# mipi_serializer2.net
KiCad netlist of a schematic drawn in Altium Designer
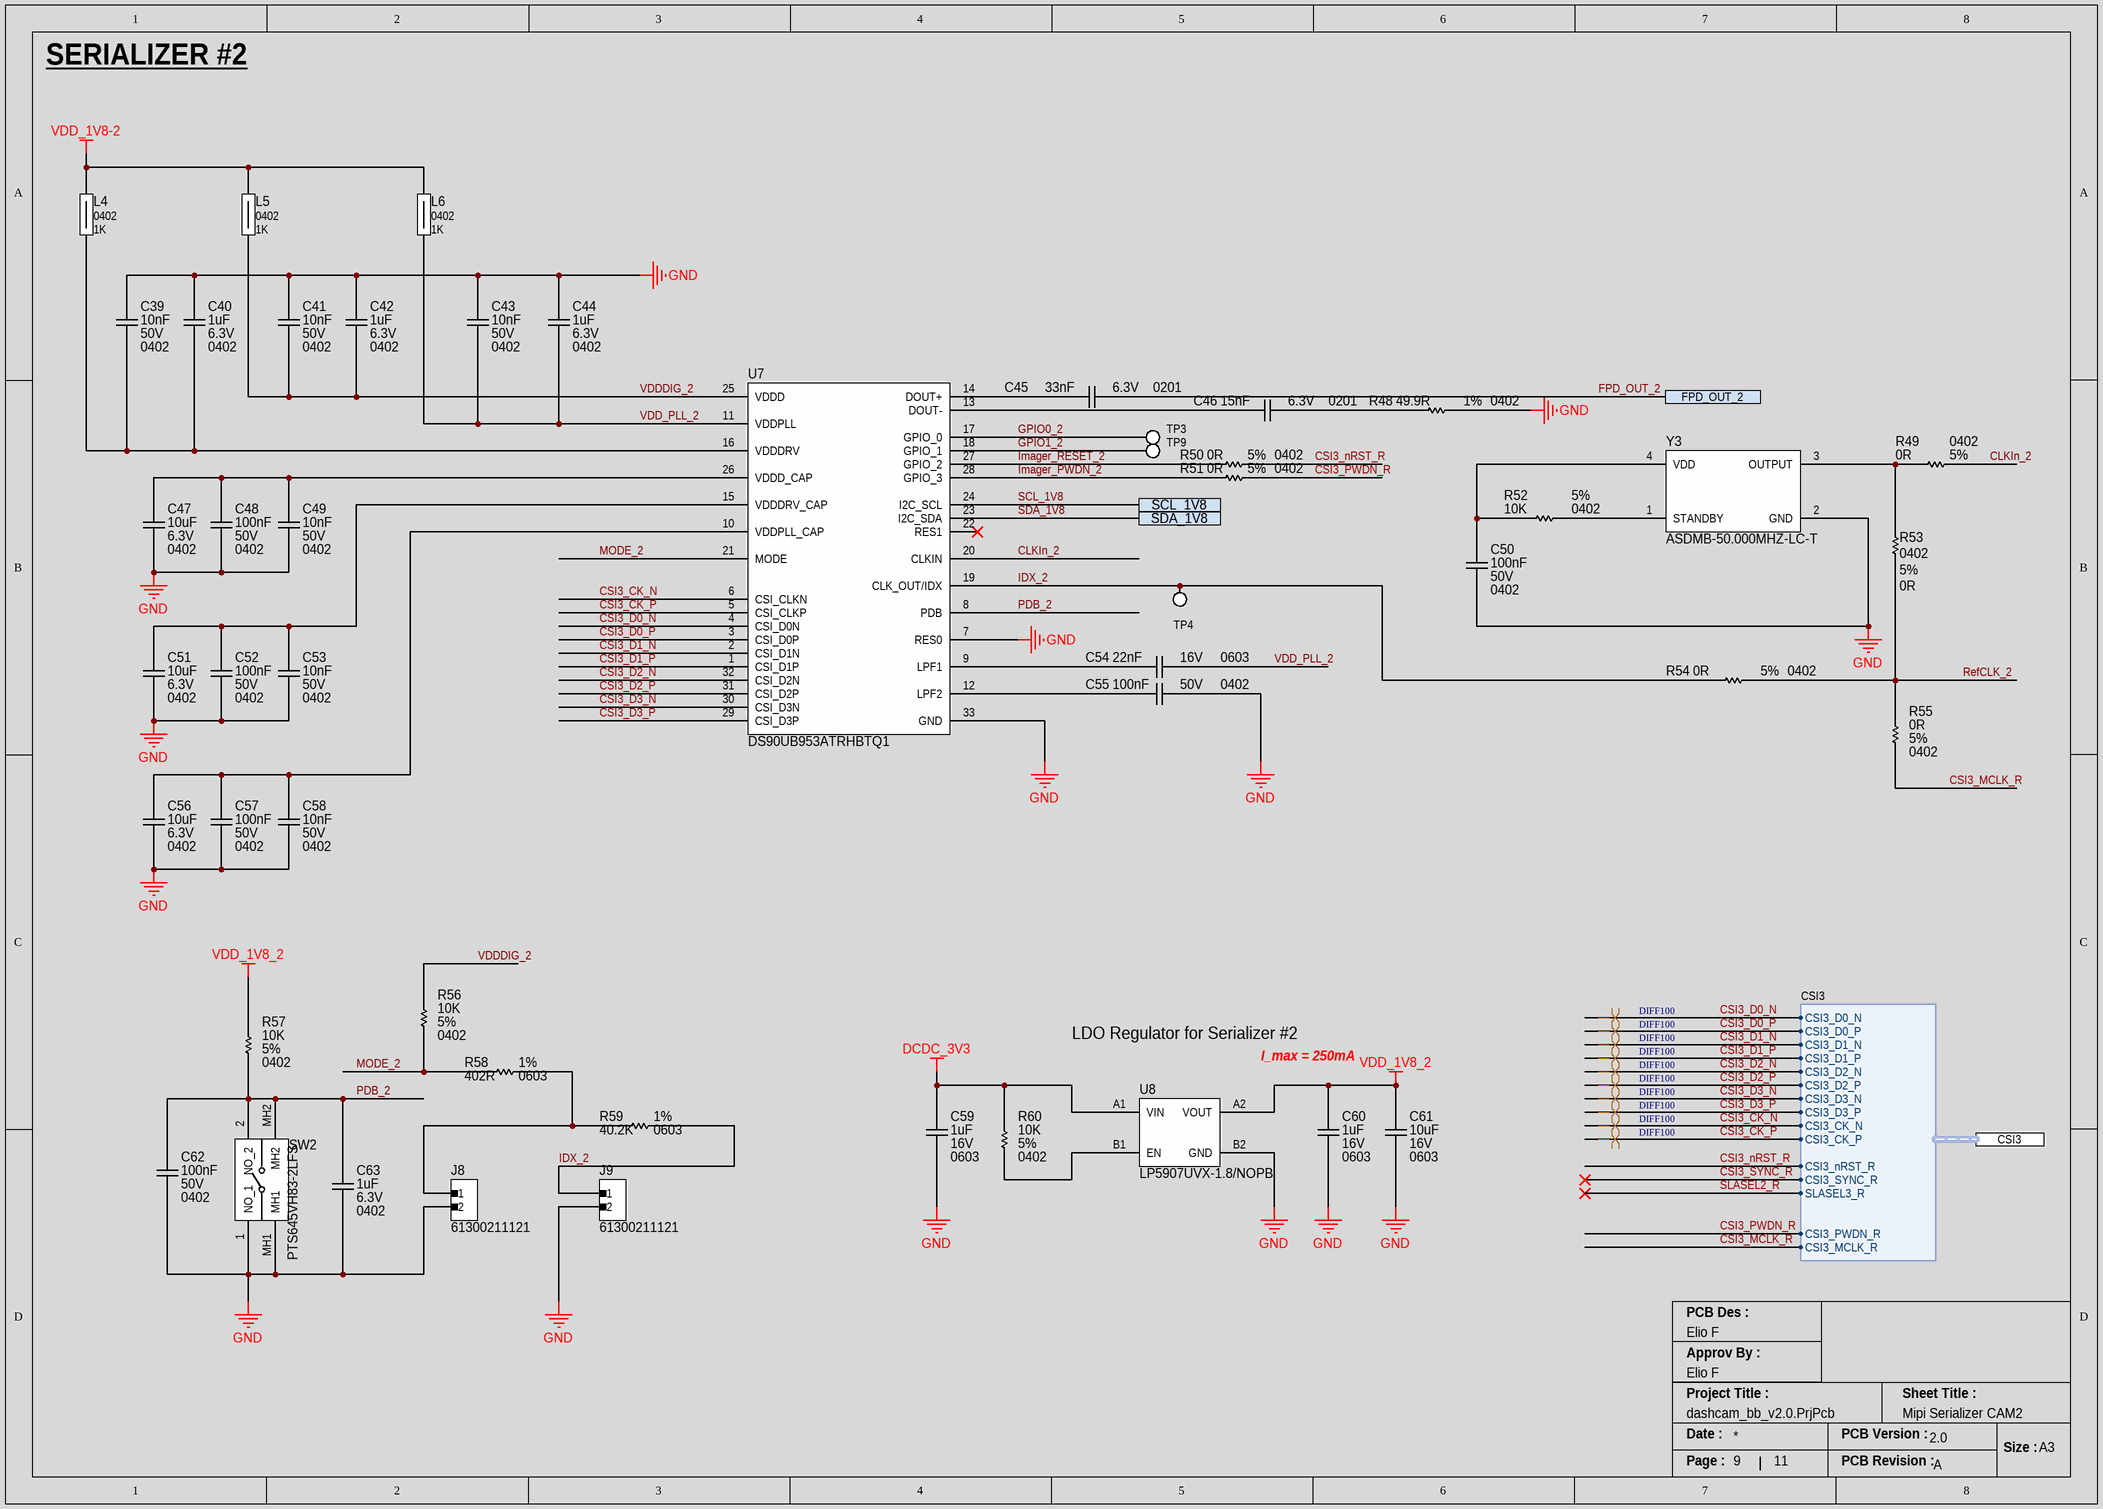
[diagram p0: mipi_serializer2.SchDoc]

(export (version "E")
  (design (tool "Eeschema 10.0.6"))
  (components
    (comp (ref "C39")
      (value "GRM155R71H103KA88D")
      (footprint "CAP_0402_CAPC1005X05N")
      (description "Multilayer Ceramic Capacitors MLCC Surface Mount 0402 0.01uF 50 Volts X7R 10%")
      (fields
        (field (name "MANUFACTURER") "Murata")
        (field (name "TOLERANCE") "10%")
        (field (name "VOLTAGE RATING") "50V")
        (field (name "CAPACITANCE") "10nF")
        (field (name "CASE/PACKAGE") "0402")
      )
      (libsource (lib "Electronic Devices_LIB") (part "CAP_10nF_50V_X7R_0402"))
    )
    (comp (ref "C40")
      (value "CL05B105KQ5NQNC")
      (footprint "CAP_0402_CAPC1005X05N")
      (description "Multilayer Ceramic Capacitor, 1 uF, 6.3 V, ï¿½ 10%, X7R, 0402 [1005 Metric]")
      (fields
        (field (name "MANUFACTURER") "Samsung")
        (field (name "TOLERANCE") "10%")
        (field (name "CAPACITANCE") "1uF")
        (field (name "VOLTAGE RATING") "6.3V")
        (field (name "CASE CODE (IMPERIAL)") "0402")
      )
      (libsource (lib "Electronic Devices_LIB") (part "CAP_1uF_6.3V_X7R_0402"))
    )
    (comp (ref "C41")
      (value "GRM155R71H103KA88D")
      (footprint "CAP_0402_CAPC1005X05N")
      (description "Multilayer Ceramic Capacitors MLCC Surface Mount 0402 0.01uF 50 Volts X7R 10%")
      (fields
        (field (name "MANUFACTURER") "Murata")
        (field (name "TOLERANCE") "10%")
        (field (name "VOLTAGE RATING") "50V")
        (field (name "CAPACITANCE") "10nF")
        (field (name "CASE/PACKAGE") "0402")
      )
      (libsource (lib "Electronic Devices_LIB") (part "CAP_10nF_50V_X7R_0402"))
    )
    (comp (ref "C42")
      (value "CL05B105KQ5NQNC")
      (footprint "CAP_0402_CAPC1005X05N")
      (description "Multilayer Ceramic Capacitor, 1 uF, 6.3 V, ï¿½ 10%, X7R, 0402 [1005 Metric]")
      (fields
        (field (name "MANUFACTURER") "Samsung")
        (field (name "TOLERANCE") "10%")
        (field (name "CAPACITANCE") "1uF")
        (field (name "VOLTAGE RATING") "6.3V")
        (field (name "CASE CODE (IMPERIAL)") "0402")
      )
      (libsource (lib "Electronic Devices_LIB") (part "CAP_1uF_6.3V_X7R_0402"))
    )
    (comp (ref "C43")
      (value "GRM155R71H103KA88D")
      (footprint "CAP_0402_CAPC1005X05N")
      (description "Multilayer Ceramic Capacitors MLCC Surface Mount 0402 0.01uF 50 Volts X7R 10%")
      (fields
        (field (name "MANUFACTURER") "Murata")
        (field (name "TOLERANCE") "10%")
        (field (name "VOLTAGE RATING") "50V")
        (field (name "CAPACITANCE") "10nF")
        (field (name "CASE/PACKAGE") "0402")
      )
      (libsource (lib "Electronic Devices_LIB") (part "CAP_10nF_50V_X7R_0402"))
    )
    (comp (ref "C44")
      (value "CL05B105KQ5NQNC")
      (footprint "CAP_0402_CAPC1005X05N")
      (description "Multilayer Ceramic Capacitor, 1 uF, 6.3 V, ï¿½ 10%, X7R, 0402 [1005 Metric]")
      (fields
        (field (name "MANUFACTURER") "Samsung")
        (field (name "TOLERANCE") "10%")
        (field (name "CAPACITANCE") "1uF")
        (field (name "VOLTAGE RATING") "6.3V")
        (field (name "CASE CODE (IMPERIAL)") "0402")
      )
      (libsource (lib "Electronic Devices_LIB") (part "CAP_1uF_6.3V_X7R_0402"))
    )
    (comp (ref "C45")
      (value "GRM033R60J333KE01D")
      (footprint "CAP_0201_CAPC0603X03N")
      (description "Multilayer Ceramic Capacitor, 0.033 uF, 6.3 V, ± 10%, X5R, 0201 [0603 Metric]")
      (fields
        (field (name "MANUFACTURER") "Murata")
        (field (name "TOLERANCE") "10%")
        (field (name "VOLTAGE RATING") "6.3V")
        (field (name "CAPACITANCE") "33nF")
        (field (name "CASE/PACKAGE") "0201")
      )
      (libsource (lib "Electronic Devices_LIB") (part "CAP_0.033uF_6.3V_X5R_0201"))
    )
    (comp (ref "C46")
      (value "GRM033R60J153KE01D")
      (footprint "CAP_0201_CAPC0603X03N")
      (description "0201 15 nF 6.3 V ±10% Tolerance X5R SMT Multilayer Ceramic Capacitor")
      (fields
        (field (name "MANUFACTURER") "Murata")
        (field (name "TOLERANCE") "10%")
        (field (name "VOLTAGE RATING") "6.3V")
        (field (name "CAPACITANCE") "15nF")
        (field (name "CASE/PACKAGE") "0201")
      )
      (libsource (lib "Electronic Devices_LIB") (part "CAP_0.015uF_6.3V_X5R_0201"))
    )
    (comp (ref "C47")
      (value "CL05A106MQ5NUNC")
      (footprint "CAP_0402_CAPC1005X05N")
      (description "Cap Ceramic 10uF 6.3V X5R 20% SMD 0402 85C T/R")
      (fields
        (field (name "MANUFACTURER") "Samsung")
        (field (name "TOLERANCE") "20%")
        (field (name "CASE/PACKAGE") "0402")
        (field (name "CAPACITANCE") "10uF")
        (field (name "VOLTAGE RATING") "6.3V")
      )
      (libsource (lib "Electronic Devices_LIB") (part "CAP_10UF_6.3V_X5R_0402"))
    )
    (comp (ref "C48")
      (value "GRM155R71H104KE14D")
      (footprint "CAP_0402_CAPC1005X05N")
      (description "Multilayer Ceramic Capacitor, 0.1 uF, 16 V, ± 10%, X7R, 0402 [1005 Metric]")
      (fields
        (field (name "MANUFACTURER") "Murata")
        (field (name "TOLERANCE") "10%")
        (field (name "VOLTAGE RATING") "50V")
        (field (name "CAPACITANCE") "100nF")
        (field (name "CASE/PACKAGE") "0402")
      )
      (libsource (lib "Electronic Devices_LIB") (part "CAP_100NF_50V_X7R_0402"))
    )
    (comp (ref "C49")
      (value "GRM155R71H103KA88D")
      (footprint "CAP_0402_CAPC1005X05N")
      (description "Multilayer Ceramic Capacitors MLCC Surface Mount 0402 0.01uF 50 Volts X7R 10%")
      (fields
        (field (name "MANUFACTURER") "Murata")
        (field (name "TOLERANCE") "10%")
        (field (name "VOLTAGE RATING") "50V")
        (field (name "CAPACITANCE") "10nF")
        (field (name "CASE/PACKAGE") "0402")
      )
      (libsource (lib "Electronic Devices_LIB") (part "CAP_10nF_50V_X7R_0402"))
    )
    (comp (ref "C50")
      (value "GRM155R71H104KE14D")
      (footprint "CAP_0402_CAPC1005X05N")
      (description "Multilayer Ceramic Capacitor, 0.1 uF, 16 V, ± 10%, X7R, 0402 [1005 Metric]")
      (fields
        (field (name "MANUFACTURER") "Murata")
        (field (name "TOLERANCE") "10%")
        (field (name "VOLTAGE RATING") "50V")
        (field (name "CAPACITANCE") "100nF")
        (field (name "CASE/PACKAGE") "0402")
      )
      (libsource (lib "Electronic Devices_LIB") (part "CAP_100NF_50V_X7R_0402"))
    )
    (comp (ref "C51")
      (value "CL05A106MQ5NUNC")
      (footprint "CAP_0402_CAPC1005X05N")
      (description "Cap Ceramic 10uF 6.3V X5R 20% SMD 0402 85C T/R")
      (fields
        (field (name "MANUFACTURER") "Samsung")
        (field (name "TOLERANCE") "20%")
        (field (name "CASE/PACKAGE") "0402")
        (field (name "CAPACITANCE") "10uF")
        (field (name "VOLTAGE RATING") "6.3V")
      )
      (libsource (lib "Electronic Devices_LIB") (part "CAP_10UF_6.3V_X5R_0402"))
    )
    (comp (ref "C52")
      (value "GRM155R71H104KE14D")
      (footprint "CAP_0402_CAPC1005X05N")
      (description "Multilayer Ceramic Capacitor, 0.1 uF, 16 V, ± 10%, X7R, 0402 [1005 Metric]")
      (fields
        (field (name "MANUFACTURER") "Murata")
        (field (name "TOLERANCE") "10%")
        (field (name "VOLTAGE RATING") "50V")
        (field (name "CAPACITANCE") "100nF")
        (field (name "CASE/PACKAGE") "0402")
      )
      (libsource (lib "Electronic Devices_LIB") (part "CAP_100NF_50V_X7R_0402"))
    )
    (comp (ref "C53")
      (value "GRM155R71H103KA88D")
      (footprint "CAP_0402_CAPC1005X05N")
      (description "Multilayer Ceramic Capacitors MLCC Surface Mount 0402 0.01uF 50 Volts X7R 10%")
      (fields
        (field (name "MANUFACTURER") "Murata")
        (field (name "TOLERANCE") "10%")
        (field (name "VOLTAGE RATING") "50V")
        (field (name "CAPACITANCE") "10nF")
        (field (name "CASE/PACKAGE") "0402")
      )
      (libsource (lib "Electronic Devices_LIB") (part "CAP_10nF_50V_X7R_0402"))
    )
    (comp (ref "C54")
      (value "C0603C223K4RACTU")
      (footprint "CAP_0603_CAPC1608X08N")
      (description "Multilayer Ceramic Capacitor, 0.022 uF, 16 V, ± 10%, X7R, 0603 [1608 Metric]")
      (fields
        (field (name "MANUFACTURER") "KEMET")
        (field (name "TOLERANCE") "10%")
        (field (name "VOLTAGE RATING (DC)") "16V")
        (field (name "CAPACITANCE") "22nF")
        (field (name "CASE/PACKAGE") "0603")
      )
      (libsource (lib "Electronic Devices_LIB") (part "CAP_22nF_16V_X7R_0603"))
    )
    (comp (ref "C55")
      (value "GRM155R71H104KE14D")
      (footprint "CAP_0402_CAPC1005X05N")
      (description "Multilayer Ceramic Capacitor, 0.1 uF, 16 V, ± 10%, X7R, 0402 [1005 Metric]")
      (fields
        (field (name "MANUFACTURER") "Murata")
        (field (name "TOLERANCE") "10%")
        (field (name "VOLTAGE RATING") "50V")
        (field (name "CAPACITANCE") "100nF")
        (field (name "CASE/PACKAGE") "0402")
      )
      (libsource (lib "Electronic Devices_LIB") (part "CAP_100NF_50V_X7R_0402"))
    )
    (comp (ref "C56")
      (value "CL05A106MQ5NUNC")
      (footprint "CAP_0402_CAPC1005X05N")
      (description "Cap Ceramic 10uF 6.3V X5R 20% SMD 0402 85C T/R")
      (fields
        (field (name "MANUFACTURER") "Samsung")
        (field (name "TOLERANCE") "20%")
        (field (name "CASE/PACKAGE") "0402")
        (field (name "CAPACITANCE") "10uF")
        (field (name "VOLTAGE RATING") "6.3V")
      )
      (libsource (lib "Electronic Devices_LIB") (part "CAP_10UF_6.3V_X5R_0402"))
    )
    (comp (ref "C57")
      (value "GRM155R71H104KE14D")
      (footprint "CAP_0402_CAPC1005X05N")
      (description "Multilayer Ceramic Capacitor, 0.1 uF, 16 V, ± 10%, X7R, 0402 [1005 Metric]")
      (fields
        (field (name "MANUFACTURER") "Murata")
        (field (name "TOLERANCE") "10%")
        (field (name "VOLTAGE RATING") "50V")
        (field (name "CAPACITANCE") "100nF")
        (field (name "CASE/PACKAGE") "0402")
      )
      (libsource (lib "Electronic Devices_LIB") (part "CAP_100NF_50V_X7R_0402"))
    )
    (comp (ref "C58")
      (value "GRM155R71H103KA88D")
      (footprint "CAP_0402_CAPC1005X05N")
      (description "Multilayer Ceramic Capacitors MLCC Surface Mount 0402 0.01uF 50 Volts X7R 10%")
      (fields
        (field (name "MANUFACTURER") "Murata")
        (field (name "TOLERANCE") "10%")
        (field (name "VOLTAGE RATING") "50V")
        (field (name "CAPACITANCE") "10nF")
        (field (name "CASE/PACKAGE") "0402")
      )
      (libsource (lib "Electronic Devices_LIB") (part "CAP_10nF_50V_X7R_0402"))
    )
    (comp (ref "C59")
      (value "CL10A105KO8NNNC")
      (footprint "CAP_0603_CAPC1608X08N")
      (description "CAP CER 1UF 16V X5R 0603")
      (fields
        (field (name "MANUFACTURER") "Samsung")
        (field (name "TOLERANCE") "10%")
        (field (name "VOLTAGE RATING") "16V")
        (field (name "CAPACITANCE") "1uF")
        (field (name "CASE/PACKAGE") "0603")
      )
      (libsource (lib "Electronic Devices_LIB") (part "CAP_1UF_16V_X5R_0603"))
    )
    (comp (ref "C60")
      (value "CL10A105KO8NNNC")
      (footprint "CAP_0603_CAPC1608X08N")
      (description "CAP CER 1UF 16V X5R 0603")
      (fields
        (field (name "MANUFACTURER") "Samsung")
        (field (name "TOLERANCE") "10%")
        (field (name "VOLTAGE RATING") "16V")
        (field (name "CAPACITANCE") "1uF")
        (field (name "CASE/PACKAGE") "0603")
      )
      (libsource (lib "Electronic Devices_LIB") (part "CAP_1UF_16V_X5R_0603"))
    )
    (comp (ref "C61")
      (value "GRM188R61C106MAALD")
      (footprint "CAP_0603_CAPC1608X08N")
      (description "0603 10 uF 16 V ±20% Tolerance X5R Multilayer Ceramic Chip Capacitor")
      (fields
        (field (name "MANUFACTURER") "Murata")
        (field (name "TOLERANCE") "20%")
        (field (name "VOLTAGE RATING") "16V")
        (field (name "CAPACITANCE") "10uF")
        (field (name "CASE/PACKAGE") "0603")
      )
      (libsource (lib "Electronic Devices_LIB") (part "CAP_10UF_16V_X5R_0603"))
    )
    (comp (ref "C62")
      (value "GRM155R71H104KE14D")
      (footprint "CAP_0402_CAPC1005X05N")
      (description "Multilayer Ceramic Capacitor, 0.1 uF, 16 V, ± 10%, X7R, 0402 [1005 Metric]")
      (fields
        (field (name "MANUFACTURER") "Murata")
        (field (name "TOLERANCE") "10%")
        (field (name "VOLTAGE RATING") "50V")
        (field (name "CAPACITANCE") "100nF")
        (field (name "CASE/PACKAGE") "0402")
      )
      (libsource (lib "Electronic Devices_LIB") (part "CAP_100NF_50V_X7R_0402"))
    )
    (comp (ref "C63")
      (value "CL05B105KQ5NQNC")
      (footprint "CAP_0402_CAPC1005X05N")
      (description "Multilayer Ceramic Capacitor, 1 uF, 6.3 V, ï¿½ 10%, X7R, 0402 [1005 Metric]")
      (fields
        (field (name "MANUFACTURER") "Samsung")
        (field (name "TOLERANCE") "10%")
        (field (name "CAPACITANCE") "1uF")
        (field (name "VOLTAGE RATING") "6.3V")
        (field (name "CASE CODE (IMPERIAL)") "0402")
      )
      (libsource (lib "Electronic Devices_LIB") (part "CAP_1uF_6.3V_X7R_0402"))
    )
    (comp (ref "J8")
      (value "61300211121")
      (footprint "HEADER_MALE_HDRV2W110P0X254_1X2_508X254X854P")
      (description "THT Vertical Pin Header WR-PHD, Pitch 2.54 mm, Single Row, 2 pins")
      (fields (field (name "MANUFACTURER") "Wurth Electronics"))
      (libsource (lib "Electronic Devices_LIB") (part "CONN_HEADER_MALE_2P_2.54_61300211121"))
    )
    (comp (ref "J9")
      (value "61300211121")
      (footprint "HEADER_MALE_HDRV2W110P0X254_1X2_508X254X854P")
      (description "THT Vertical Pin Header WR-PHD, Pitch 2.54 mm, Single Row, 2 pins")
      (fields (field (name "MANUFACTURER") "Wurth Electronics"))
      (libsource (lib "Electronic Devices_LIB") (part "CONN_HEADER_MALE_2P_2.54_61300211121"))
    )
    (comp (ref "L4")
      (value "*BLM15AX102SN1D")
      (footprint "IND_0402")
      (description "Ferrite Beads Multi-Layer 1KOhm 25% 100MHz 350mA 490mOhm DCR 0402 Paper T/R")
      (fields
        (field (name "MANUFACTURER") "Murata")
        (field (name "MANUFACTURER PART NUMBER") "BLM15AX102SN1D")
        (field (name "CASE/PACKAGE") "0402")
        (field (name "IMPEDANCE") "1K")
      )
      (libsource (lib "Electronic Devices_LIB") (part "IND_FERRITE_BEADS_1K_350mA_BLM15AX102SN1D"))
    )
    (comp (ref "L5")
      (value "*BLM15AX102SN1D")
      (footprint "IND_0402")
      (description "Ferrite Beads Multi-Layer 1KOhm 25% 100MHz 350mA 490mOhm DCR 0402 Paper T/R")
      (fields
        (field (name "MANUFACTURER") "Murata")
        (field (name "MANUFACTURER PART NUMBER") "BLM15AX102SN1D")
        (field (name "CASE/PACKAGE") "0402")
        (field (name "IMPEDANCE") "1K")
      )
      (libsource (lib "Electronic Devices_LIB") (part "IND_FERRITE_BEADS_1K_350mA_BLM15AX102SN1D"))
    )
    (comp (ref "L6")
      (value "*BLM15AX102SN1D")
      (footprint "IND_0402")
      (description "Ferrite Beads Multi-Layer 1KOhm 25% 100MHz 350mA 490mOhm DCR 0402 Paper T/R")
      (fields
        (field (name "MANUFACTURER") "Murata")
        (field (name "MANUFACTURER PART NUMBER") "BLM15AX102SN1D")
        (field (name "CASE/PACKAGE") "0402")
        (field (name "IMPEDANCE") "1K")
      )
      (libsource (lib "Electronic Devices_LIB") (part "IND_FERRITE_BEADS_1K_350mA_BLM15AX102SN1D"))
    )
    (comp (ref "R48")
      (value "CR0402-FX-49R9GLF")
      (footprint "RES_0402_RESC1005X04N")
      (description "SMD Chip Resistor, 49.9 Ohm, ± 1%, 63 mW, 0402 [1005 Metric], Thick Film, General Purpose")
      (fields
        (field (name "MANUFACTURER") "Bourns")
        (field (name "RESISTANCE") "49.9R")
        (field (name "TOLERANCE") "1%")
        (field (name "CASE/PACKAGE") "0402")
      )
      (libsource (lib "Electronic Devices_LIB") (part "RES_49.9R_1%_63mW_0402"))
    )
    (comp (ref "R49")
      (value "ERJ-2GE0R00X")
      (footprint "RES_0402_RESC1005X04N")
      (description "SMD Chip Resistor, Jumper, 0 ohm, 100 mW, 0402 [1005 Metric], Thick Film, General Purpose")
      (fields
        (field (name "MANUFACTURER") "Panasonic")
        (field (name "CASE CODE (IMPERIAL)") "0402")
        (field (name "TOLERANCE") "5%")
        (field (name "RESISTANCE") "0R")
      )
      (libsource (lib "Electronic Devices_LIB") (part "RES_0R_5%_100mW_0402"))
    )
    (comp (ref "R50")
      (value "ERJ-2GE0R00X")
      (footprint "RES_0402_RESC1005X04N")
      (description "SMD Chip Resistor, Jumper, 0 ohm, 100 mW, 0402 [1005 Metric], Thick Film, General Purpose")
      (fields
        (field (name "MANUFACTURER") "Panasonic")
        (field (name "CASE CODE (IMPERIAL)") "0402")
        (field (name "TOLERANCE") "5%")
        (field (name "RESISTANCE") "0R")
      )
      (libsource (lib "Electronic Devices_LIB") (part "RES_0R_5%_100mW_0402"))
    )
    (comp (ref "R51")
      (value "ERJ-2GE0R00X")
      (footprint "RES_0402_RESC1005X04N")
      (description "SMD Chip Resistor, Jumper, 0 ohm, 100 mW, 0402 [1005 Metric], Thick Film, General Purpose")
      (fields
        (field (name "MANUFACTURER") "Panasonic")
        (field (name "CASE CODE (IMPERIAL)") "0402")
        (field (name "TOLERANCE") "5%")
        (field (name "RESISTANCE") "0R")
      )
      (libsource (lib "Electronic Devices_LIB") (part "RES_0R_5%_100mW_0402"))
    )
    (comp (ref "R52")
      (value "ERJ-2GEJ103X")
      (footprint "RES_0402_RESC1005X04N")
      (description "Res Thick Film 0402 10K Ohm 5% 1/10W ±200ppm/°C Molded SMD Punched Carrier T/R")
      (fields
        (field (name "MANUFACTURER") "Panasonic")
        (field (name "TOLERANCE") "5%")
        (field (name "RESISTANCE") "10K")
        (field (name "CASE/PACKAGE") "0402")
      )
      (libsource (lib "Electronic Devices_LIB") (part "RES_10K_5%_100mW_0402"))
    )
    (comp (ref "R53")
      (value "ERJ-2GE0R00X")
      (footprint "RES_0402_RESC1005X04N")
      (description "SMD Chip Resistor, Jumper, 0 ohm, 100 mW, 0402 [1005 Metric], Thick Film, General Purpose")
      (fields
        (field (name "MANUFACTURER") "Panasonic")
        (field (name "CASE CODE (IMPERIAL)") "0402")
        (field (name "TOLERANCE") "5%")
        (field (name "RESISTANCE") "0R")
      )
      (libsource (lib "Electronic Devices_LIB") (part "RES_0R_5%_100mW_0402"))
    )
    (comp (ref "R54")
      (value "ERJ-2GE0R00X")
      (footprint "RES_0402_RESC1005X04N")
      (description "SMD Chip Resistor, Jumper, 0 ohm, 100 mW, 0402 [1005 Metric], Thick Film, General Purpose")
      (fields
        (field (name "MANUFACTURER") "Panasonic")
        (field (name "CASE CODE (IMPERIAL)") "0402")
        (field (name "TOLERANCE") "5%")
        (field (name "RESISTANCE") "0R")
      )
      (libsource (lib "Electronic Devices_LIB") (part "RES_0R_5%_100mW_0402"))
    )
    (comp (ref "R55")
      (value "ERJ-2GE0R00X")
      (footprint "RES_0402_RESC1005X04N")
      (description "SMD Chip Resistor, Jumper, 0 ohm, 100 mW, 0402 [1005 Metric], Thick Film, General Purpose")
      (fields
        (field (name "MANUFACTURER") "Panasonic")
        (field (name "CASE CODE (IMPERIAL)") "0402")
        (field (name "TOLERANCE") "5%")
        (field (name "RESISTANCE") "0R")
      )
      (libsource (lib "Electronic Devices_LIB") (part "RES_0R_5%_100mW_0402"))
    )
    (comp (ref "R56")
      (value "ERJ-2GEJ103X")
      (footprint "RES_0402_RESC1005X04N")
      (description "Res Thick Film 0402 10K Ohm 5% 1/10W ±200ppm/°C Molded SMD Punched Carrier T/R")
      (fields
        (field (name "MANUFACTURER") "Panasonic")
        (field (name "TOLERANCE") "5%")
        (field (name "RESISTANCE") "10K")
        (field (name "CASE/PACKAGE") "0402")
      )
      (libsource (lib "Electronic Devices_LIB") (part "RES_10K_5%_100mW_0402"))
    )
    (comp (ref "R57")
      (value "ERJ-2GEJ103X")
      (footprint "RES_0402_RESC1005X04N")
      (description "Res Thick Film 0402 10K Ohm 5% 1/10W ±200ppm/°C Molded SMD Punched Carrier T/R")
      (fields
        (field (name "MANUFACTURER") "Panasonic")
        (field (name "TOLERANCE") "5%")
        (field (name "RESISTANCE") "10K")
        (field (name "CASE/PACKAGE") "0402")
      )
      (libsource (lib "Electronic Devices_LIB") (part "RES_10K_5%_100mW_0402"))
    )
    (comp (ref "R58")
      (value "CRCW0603402RFKEA")
      (footprint "RES_0603_RESC1608X04N")
      (description "CRCW Series 0603 0.1 W 402 Ohm ±1 % ±100 ppm/K SMT Thick Film Chip Resistor")
      (fields
        (field (name "MANUFACTURER") "Vishay")
        (field (name "TOLERANCE") "1%")
        (field (name "RESISTANCE") "402R")
        (field (name "CASE/PACKAGE") "0603")
      )
      (libsource (lib "Electronic Devices_LIB") (part "RES_402R_1%_100mW_0402"))
    )
    (comp (ref "R59")
      (value "RC0603FR-0740K2L")
      (footprint "RES_0603_RESC1608X04N")
      (description "Res General Purpose Thick Film 0603 40.2K Ohm 1% 1/10W ±100ppm/°C Molded SMD Paper T/R")
      (fields
        (field (name "MANUFACTURER") "Yageo")
        (field (name "TOLERANCE") "1%")
        (field (name "RESISTANCE") "40.2K")
        (field (name "CASE/PACKAGE") "0603")
      )
      (libsource (lib "Electronic Devices_LIB") (part "RES_40.2K_1%_100mW_0603"))
    )
    (comp (ref "R60")
      (value "ERJ-2GEJ103X")
      (footprint "RES_0402_RESC1005X04N")
      (description "Res Thick Film 0402 10K Ohm 5% 1/10W ±200ppm/°C Molded SMD Punched Carrier T/R")
      (fields
        (field (name "MANUFACTURER") "Panasonic")
        (field (name "TOLERANCE") "5%")
        (field (name "RESISTANCE") "10K")
        (field (name "CASE/PACKAGE") "0402")
      )
      (libsource (lib "Electronic Devices_LIB") (part "RES_10K_5%_100mW_0402"))
    )
    (comp (ref "SW2")
      (value "PTS645VH83-2LFS")
      (footprint "SW_RA_PTS645VH832LFS")
      (description "Switch Tactile N.O SPST Round Button PC Pins 0.05A 12VDC 100000Cycle 1.96N Thru-Hole Bulk")
      (fields (field (name "MANUFACTURER") "ITT C&K"))
      (libsource (lib "Electronic Devices_LIB") (part "SWITCH_SPST_NO_RA_PTS645VH83-2LFS"))
    )
    (comp (ref "TP3")
      (value "NO COMPONENT")
      (footprint "TP_PAD_1.6MM_SMD_ROUND")
      (description "Test Point, SMD pad, round, 1.5mm, 1.6mm, 3mm diameter")
      (libsource (lib "Electronic Devices_LIB") (part "TP_PAD_SMD_Round"))
    )
    (comp (ref "TP4")
      (value "NO COMPONENT")
      (footprint "TP_PAD_1.6MM_SMD_ROUND")
      (description "Test Point, SMD pad, round, 1.5mm, 1.6mm, 3mm diameter")
      (libsource (lib "Electronic Devices_LIB") (part "TP_PAD_SMD_Round"))
    )
    (comp (ref "TP9")
      (value "NO COMPONENT")
      (footprint "TP_PAD_1.6MM_SMD_ROUND")
      (description "Test Point, SMD pad, round, 1.5mm, 1.6mm, 3mm diameter")
      (libsource (lib "Electronic Devices_LIB") (part "TP_PAD_SMD_Round"))
    )
    (comp (ref "U7")
      (value "DS90UB953ATRHBTQ1")
      (footprint "IC_SERIALIZER_QFN50P500X500X100-33N-D")
      (description "FPD-Link III 4.16-Gbps serializer with CSI-2 interface 32-VQFN -40 to 125")
      (fields (field (name "MANUFACTURER") "Texas Instruments"))
      (libsource (lib "Electronic Devices_LIB") (part "IC_MIPI_SERIALIZER_DS90UB953ATRHBTQ1"))
    )
    (comp (ref "U8")
      (value "LP5907UVX-1.8/NOPB")
      (footprint "IC_REG_LDO_BGA4C35P2X2_71X71X40")
      (description "Low Dropout Regulators(LDO) Positive Fixed 200mV @ 250mA 5.5V 1.8V 250mA DSBGA-4 RoHS")
      (fields (field (name "MANUFACTURER") "Texas Instruments"))
      (libsource (lib "Electronic Devices_LIB") (part "IC_REG_LDO_1.8V_250mA_LP5907UVX-1.8/NOPB"))
    )
    (comp (ref "Y3")
      (value "ASDMB-50.000MHZ-LC-T")
      (footprint "XTAL_ASDMB-50.000MHZ-LC-T")
      (fields (field (name "MANUFACTURER") "Abracon"))
      (libsource (lib "Electronic Devices_LIB") (part "CRYSTAL_ABRACON_50MHz_ASDMB-50.000MHZ-LC-T"))
    )
  )
  (nets
    (net (code "2") (name "/CLKIn_2") (class "Default")
      (node (ref "R49") (pin "2") (pinfunction "2_2") (pintype "passive"))
      (node (ref "U7") (pin "20") (pinfunction "CLKIN_20") (pintype "passive"))
    )
    (net (code "3") (name "/CSI3_CK_N") (class "Default")
      (node (ref "U7") (pin "6") (pinfunction "CSI_CLKN_6") (pintype "passive"))
    )
    (net (code "4") (name "/CSI3_CK_P") (class "Default")
      (node (ref "U7") (pin "5") (pinfunction "CSI_CLKP_5") (pintype "passive"))
    )
    (net (code "5") (name "/CSI3_D0_N") (class "Default")
      (node (ref "U7") (pin "4") (pinfunction "CSI_D0N_4") (pintype "passive"))
    )
    (net (code "6") (name "/CSI3_D0_P") (class "Default")
      (node (ref "U7") (pin "3") (pinfunction "CSI_D0P_3") (pintype "passive"))
    )
    (net (code "7") (name "/CSI3_D1_N") (class "Default")
      (node (ref "U7") (pin "2") (pinfunction "CSI_D1N_2") (pintype "passive"))
    )
    (net (code "8") (name "/CSI3_D1_P") (class "Default")
      (node (ref "U7") (pin "1") (pinfunction "CSI_D1P_1") (pintype "passive"))
    )
    (net (code "9") (name "/CSI3_D2_N") (class "Default")
      (node (ref "U7") (pin "32") (pinfunction "CSI_D2N_32") (pintype "passive"))
    )
    (net (code "10") (name "/CSI3_D2_P") (class "Default")
      (node (ref "U7") (pin "31") (pinfunction "CSI_D2P_31") (pintype "passive"))
    )
    (net (code "11") (name "/CSI3_D3_N") (class "Default")
      (node (ref "U7") (pin "30") (pinfunction "CSI_D3N_30") (pintype "passive"))
    )
    (net (code "12") (name "/CSI3_D3_P") (class "Default")
      (node (ref "U7") (pin "29") (pinfunction "CSI_D3P_29") (pintype "passive"))
    )
    (net (code "13") (name "/CSI3_MCLK_R") (class "Default")
      (node (ref "R55") (pin "1") (pinfunction "1_1") (pintype "passive"))
    )
    (net (code "14") (name "/CSI3_PWDN_R") (class "Default")
      (node (ref "R51") (pin "2") (pinfunction "2_2") (pintype "passive"))
    )
    (net (code "16") (name "/CSI3_nRST_R") (class "Default")
      (node (ref "R50") (pin "2") (pinfunction "2_2") (pintype "passive"))
    )
    (net (code "17") (name "/FPD_OUT_2") (class "Default")
      (node (ref "C45") (pin "2") (pinfunction "2_2") (pintype "passive"))
    )
    (net (code "18") (name "/GPIO0_2") (class "Default")
      (node (ref "TP3") (pin "1") (pinfunction "1_1") (pintype "passive"))
      (node (ref "U7") (pin "17") (pinfunction "GPIO_0_17") (pintype "passive"))
    )
    (net (code "19") (name "/GPIO1_2") (class "Default")
      (node (ref "TP9") (pin "1") (pinfunction "1_1") (pintype "passive"))
      (node (ref "U7") (pin "18") (pinfunction "GPIO_1_18") (pintype "passive"))
    )
    (net (code "20") (name "/IDX_2") (class "Default")
      (node (ref "J9") (pin "1") (pinfunction "1_1") (pintype "passive"))
      (node (ref "R54") (pin "2") (pinfunction "2_2") (pintype "passive"))
      (node (ref "R59") (pin "2") (pinfunction "2_2") (pintype "passive"))
      (node (ref "TP4") (pin "1") (pinfunction "1_1") (pintype "passive"))
      (node (ref "U7") (pin "19") (pinfunction "CLK_OUT/IDX_19") (pintype "passive"))
    )
    (net (code "21") (name "/Imager_PWDN_2") (class "Default")
      (node (ref "R51") (pin "1") (pinfunction "1_1") (pintype "passive"))
      (node (ref "U7") (pin "28") (pinfunction "GPIO_3_28") (pintype "passive"))
    )
    (net (code "22") (name "/Imager_RESET_2") (class "Default")
      (node (ref "R50") (pin "1") (pinfunction "1_1") (pintype "passive"))
      (node (ref "U7") (pin "27") (pinfunction "GPIO_2_27") (pintype "passive"))
    )
    (net (code "23") (name "/MODE_2") (class "Default")
      (node (ref "R56") (pin "1") (pinfunction "1_1") (pintype "passive"))
      (node (ref "R58") (pin "1") (pinfunction "1_1") (pintype "passive"))
      (node (ref "U7") (pin "21") (pinfunction "MODE_21") (pintype "passive"))
    )
    (net (code "24") (name "/PDB_2") (class "Default")
      (node (ref "C62") (pin "2") (pinfunction "2_2") (pintype "passive"))
      (node (ref "C63") (pin "2") (pinfunction "2_2") (pintype "passive"))
      (node (ref "R57") (pin "1") (pinfunction "1_1") (pintype "passive"))
      (node (ref "SW2") (pin "2") (pinfunction "NO_2_2") (pintype "passive"))
      (node (ref "SW2") (pin "MH2") (pinfunction "MH2_MH2") (pintype "passive"))
      (node (ref "U7") (pin "8") (pinfunction "PDB_8") (pintype "passive"))
    )
    (net (code "25") (name "/RefCLK_2") (class "Default")
      (node (ref "R53") (pin "1") (pinfunction "1_1") (pintype "passive"))
      (node (ref "R54") (pin "1") (pinfunction "1_1") (pintype "passive"))
      (node (ref "R55") (pin "2") (pinfunction "2_2") (pintype "passive"))
    )
    (net (code "26") (name "/SCL_1V8") (class "Default")
      (node (ref "U7") (pin "24") (pinfunction "I2C_SCL_24") (pintype "passive"))
    )
    (net (code "27") (name "/SDA_1V8") (class "Default")
      (node (ref "U7") (pin "23") (pinfunction "I2C_SDA_23") (pintype "passive"))
    )
    (net (code "29") (name "/VDDDIG_2") (class "Default")
      (node (ref "C41") (pin "1") (pinfunction "1_1") (pintype "passive"))
      (node (ref "C42") (pin "1") (pinfunction "1_1") (pintype "passive"))
      (node (ref "L5") (pin "1") (pinfunction "1_1") (pintype "passive"))
      (node (ref "R56") (pin "2") (pinfunction "2_2") (pintype "passive"))
      (node (ref "U7") (pin "25") (pinfunction "VDDD_25") (pintype "passive"))
    )
    (net (code "30") (name "/VDD_PLL_2") (class "Default")
      (node (ref "C43") (pin "1") (pinfunction "1_1") (pintype "passive"))
      (node (ref "C44") (pin "1") (pinfunction "1_1") (pintype "passive"))
      (node (ref "C54") (pin "2") (pinfunction "2_2") (pintype "passive"))
      (node (ref "L6") (pin "1") (pinfunction "1_1") (pintype "passive"))
      (node (ref "U7") (pin "11") (pinfunction "VDDPLL_11") (pintype "passive"))
    )
    (net (code "32") (name "DCDC_3V3") (class "Default")
      (node (ref "C59") (pin "2") (pinfunction "2_2") (pintype "passive"))
      (node (ref "R60") (pin "2") (pinfunction "2_2") (pintype "passive"))
      (node (ref "U8") (pin "A1") (pinfunction "VIN_A1") (pintype "passive"))
    )
    (net (code "33") (name "GND") (class "Default")
      (node (ref "C39") (pin "2") (pinfunction "2_2") (pintype "passive"))
      (node (ref "C40") (pin "2") (pinfunction "2_2") (pintype "passive"))
      (node (ref "C41") (pin "2") (pinfunction "2_2") (pintype "passive"))
      (node (ref "C42") (pin "2") (pinfunction "2_2") (pintype "passive"))
      (node (ref "C43") (pin "2") (pinfunction "2_2") (pintype "passive"))
      (node (ref "C44") (pin "2") (pinfunction "2_2") (pintype "passive"))
      (node (ref "C47") (pin "1") (pinfunction "1_1") (pintype "passive"))
      (node (ref "C48") (pin "1") (pinfunction "1_1") (pintype "passive"))
      (node (ref "C49") (pin "1") (pinfunction "1_1") (pintype "passive"))
      (node (ref "C50") (pin "1") (pinfunction "1_1") (pintype "passive"))
      (node (ref "C51") (pin "1") (pinfunction "1_1") (pintype "passive"))
      (node (ref "C52") (pin "1") (pinfunction "1_1") (pintype "passive"))
      (node (ref "C53") (pin "1") (pinfunction "1_1") (pintype "passive"))
      (node (ref "C55") (pin "1") (pinfunction "1_1") (pintype "passive"))
      (node (ref "C56") (pin "1") (pinfunction "1_1") (pintype "passive"))
      (node (ref "C57") (pin "1") (pinfunction "1_1") (pintype "passive"))
      (node (ref "C58") (pin "1") (pinfunction "1_1") (pintype "passive"))
      (node (ref "C59") (pin "1") (pinfunction "1_1") (pintype "passive"))
      (node (ref "C60") (pin "1") (pinfunction "1_1") (pintype "passive"))
      (node (ref "C61") (pin "1") (pinfunction "1_1") (pintype "passive"))
      (node (ref "C62") (pin "1") (pinfunction "1_1") (pintype "passive"))
      (node (ref "C63") (pin "1") (pinfunction "1_1") (pintype "passive"))
      (node (ref "J8") (pin "2") (pinfunction "2_2") (pintype "passive"))
      (node (ref "J9") (pin "2") (pinfunction "2_2") (pintype "passive"))
      (node (ref "R48") (pin "2") (pinfunction "2_2") (pintype "passive"))
      (node (ref "SW2") (pin "1") (pinfunction "NO_1_1") (pintype "passive"))
      (node (ref "SW2") (pin "MH1") (pinfunction "MH1_MH1") (pintype "passive"))
      (node (ref "U7") (pin "33") (pinfunction "GND_33") (pintype "passive"))
      (node (ref "U7") (pin "7") (pinfunction "RES0_7") (pintype "passive"))
      (node (ref "U8") (pin "B2") (pinfunction "GND_B2") (pintype "passive"))
      (node (ref "Y3") (pin "2") (pinfunction "GND_2") (pintype "power_in"))
    )
    (net (code "34") (name "Net-(C46-Pad2)") (class "Default")
      (node (ref "C46") (pin "2") (pinfunction "2_2") (pintype "passive"))
      (node (ref "R48") (pin "1") (pinfunction "1_1") (pintype "passive"))
    )
    (net (code "35") (name "Net-(J8-Pad1)") (class "Default")
      (node (ref "J8") (pin "1") (pinfunction "1_1") (pintype "passive"))
      (node (ref "R58") (pin "2") (pinfunction "2_2") (pintype "passive"))
      (node (ref "R59") (pin "1") (pinfunction "1_1") (pintype "passive"))
    )
    (net (code "36") (name "Net-(U7-DOUT+)") (class "Default")
      (node (ref "C45") (pin "1") (pinfunction "1_1") (pintype "passive"))
      (node (ref "U7") (pin "14") (pinfunction "DOUT+_14") (pintype "passive"))
    )
    (net (code "37") (name "Net-(U7-DOUT-)") (class "Default")
      (node (ref "C46") (pin "1") (pinfunction "1_1") (pintype "passive"))
      (node (ref "U7") (pin "13") (pinfunction "DOUT-_13") (pintype "passive"))
    )
    (net (code "38") (name "Net-(U7-LPF1)") (class "Default")
      (node (ref "C54") (pin "1") (pinfunction "1_1") (pintype "passive"))
      (node (ref "U7") (pin "9") (pinfunction "LPF1_9") (pintype "passive"))
    )
    (net (code "39") (name "Net-(U7-LPF2)") (class "Default")
      (node (ref "C55") (pin "2") (pinfunction "2_2") (pintype "passive"))
      (node (ref "U7") (pin "12") (pinfunction "LPF2_12") (pintype "passive"))
    )
    (net (code "40") (name "Net-(U7-VDDDRV)") (class "Default")
      (node (ref "C39") (pin "1") (pinfunction "1_1") (pintype "passive"))
      (node (ref "C40") (pin "1") (pinfunction "1_1") (pintype "passive"))
      (node (ref "L4") (pin "1") (pinfunction "1_1") (pintype "passive"))
      (node (ref "U7") (pin "16") (pinfunction "VDDDRV_16") (pintype "passive"))
    )
    (net (code "41") (name "Net-(U7-VDDDRV_CAP)") (class "Default")
      (node (ref "C51") (pin "2") (pinfunction "2_2") (pintype "passive"))
      (node (ref "C52") (pin "2") (pinfunction "2_2") (pintype "passive"))
      (node (ref "C53") (pin "2") (pinfunction "2_2") (pintype "passive"))
      (node (ref "U7") (pin "15") (pinfunction "VDDDRV_CAP_15") (pintype "passive"))
    )
    (net (code "42") (name "Net-(U7-VDDD_CAP)") (class "Default")
      (node (ref "C47") (pin "2") (pinfunction "2_2") (pintype "passive"))
      (node (ref "C48") (pin "2") (pinfunction "2_2") (pintype "passive"))
      (node (ref "C49") (pin "2") (pinfunction "2_2") (pintype "passive"))
      (node (ref "U7") (pin "26") (pinfunction "VDDD_CAP_26") (pintype "passive"))
    )
    (net (code "43") (name "Net-(U7-VDDPLL_CAP)") (class "Default")
      (node (ref "C56") (pin "2") (pinfunction "2_2") (pintype "passive"))
      (node (ref "C57") (pin "2") (pinfunction "2_2") (pintype "passive"))
      (node (ref "C58") (pin "2") (pinfunction "2_2") (pintype "passive"))
      (node (ref "U7") (pin "10") (pinfunction "VDDPLL_CAP_10") (pintype "passive"))
    )
    (net (code "44") (name "Net-(U8-EN)") (class "Default")
      (node (ref "R60") (pin "1") (pinfunction "1_1") (pintype "passive"))
      (node (ref "U8") (pin "B1") (pinfunction "EN_B1") (pintype "passive"))
    )
    (net (code "45") (name "Net-(Y3-OUTPUT)") (class "Default")
      (node (ref "R49") (pin "1") (pinfunction "1_1") (pintype "passive"))
      (node (ref "R53") (pin "2") (pinfunction "2_2") (pintype "passive"))
      (node (ref "Y3") (pin "3") (pinfunction "OUTPUT_3") (pintype "passive"))
    )
    (net (code "46") (name "Net-(Y3-STANDBY)") (class "Default")
      (node (ref "R52") (pin "2") (pinfunction "2_2") (pintype "passive"))
      (node (ref "Y3") (pin "1") (pinfunction "STANDBY_1") (pintype "passive"))
    )
    (net (code "47") (name "Net-(Y3-VDD)") (class "Default")
      (node (ref "C50") (pin "2") (pinfunction "2_2") (pintype "passive"))
      (node (ref "R52") (pin "1") (pinfunction "1_1") (pintype "passive"))
      (node (ref "Y3") (pin "4") (pinfunction "VDD_4") (pintype "power_in"))
    )
    (net (code "48") (name "VDD_1V8-2") (class "Default")
      (node (ref "L4") (pin "2") (pinfunction "2_2") (pintype "passive"))
      (node (ref "L5") (pin "2") (pinfunction "2_2") (pintype "passive"))
      (node (ref "L6") (pin "2") (pinfunction "2_2") (pintype "passive"))
    )
    (net (code "49") (name "VDD_1V8_2") (class "Default")
      (node (ref "C60") (pin "2") (pinfunction "2_2") (pintype "passive"))
      (node (ref "C61") (pin "2") (pinfunction "2_2") (pintype "passive"))
      (node (ref "R57") (pin "2") (pinfunction "2_2") (pintype "passive"))
      (node (ref "U8") (pin "A2") (pinfunction "VOUT_A2") (pintype "passive"))
    )
    (net (code "50") (name "unconnected-(U7-RES1-Pad22)") (class "Default")
      (node (ref "U7") (pin "22") (pinfunction "RES1_22") (pintype "passive+no_connect"))
    )
  )
)
